# Driver.net
KiCad netlist of a schematic drawn in EAGLE
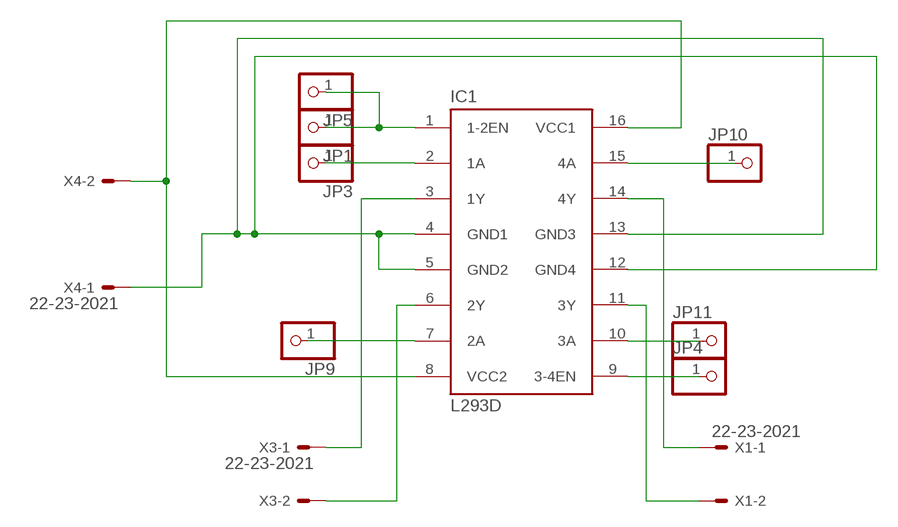
[diagram p0: schematic, sheet 1]

(export (version "E")
  (design (tool "Eeschema 10.0.6"))
  (components
    (comp (ref "IC1")
      (value "L293D")
      (footprint "eagle-import:DIL16")
      (libsource (lib "eagle-import") (part "L293D"))
    )
    (comp (ref "JP1")
      (value "PINHD-1X1")
      (footprint "eagle-import:1X01")
      (libsource (lib "eagle-import") (part "PINHD-1X1"))
    )
    (comp (ref "JP3")
      (value "PINHD-1X1")
      (footprint "eagle-import:1X01")
      (libsource (lib "eagle-import") (part "PINHD-1X1"))
    )
    (comp (ref "JP4")
      (value "PINHD-1X1")
      (footprint "eagle-import:1X01")
      (libsource (lib "eagle-import") (part "PINHD-1X1"))
    )
    (comp (ref "JP5")
      (value "PINHD-1X1")
      (footprint "eagle-import:1X01")
      (libsource (lib "eagle-import") (part "PINHD-1X1"))
    )
    (comp (ref "JP9")
      (value "PINHD-1X1")
      (footprint "eagle-import:1X01")
      (libsource (lib "eagle-import") (part "PINHD-1X1"))
    )
    (comp (ref "JP10")
      (value "PINHD-1X1")
      (footprint "eagle-import:1X01")
      (libsource (lib "eagle-import") (part "PINHD-1X1"))
    )
    (comp (ref "JP11")
      (value "PINHD-1X1")
      (footprint "eagle-import:1X01")
      (libsource (lib "eagle-import") (part "PINHD-1X1"))
    )
    (comp (ref "X1")
      (value "22-23-2021")
      (footprint "eagle-import:22-23-2021")
      (fields (field (name "MF") "MOLEX"))
      (libsource (lib "eagle-import") (part "22-23-2021"))
    )
    (comp (ref "X3")
      (value "22-23-2021")
      (footprint "eagle-import:22-23-2021")
      (fields (field (name "MF") "MOLEX"))
      (libsource (lib "eagle-import") (part "22-23-2021"))
    )
    (comp (ref "X4")
      (value "22-23-2021")
      (footprint "eagle-import:22-23-2021")
      (fields (field (name "MF") "MOLEX"))
      (libsource (lib "eagle-import") (part "22-23-2021"))
    )
  )
  (nets
    (net (code "1") (name "Net-(IC1-1-2EN)") (class "Default")
      (node (ref "IC1") (pin "1") (pinfunction "1-2EN_1") (pintype "input"))
      (node (ref "JP1") (pin "1") (pinfunction "1_1") (pintype "passive"))
      (node (ref "JP5") (pin "1") (pinfunction "1_1") (pintype "passive"))
    )
    (net (code "2") (name "Net-(IC1-1A)") (class "Default")
      (node (ref "IC1") (pin "2") (pinfunction "1A_2") (pintype "input"))
      (node (ref "JP3") (pin "1") (pinfunction "1_1") (pintype "passive"))
    )
    (net (code "3") (name "Net-(IC1-1Y)") (class "Default")
      (node (ref "IC1") (pin "3") (pinfunction "1Y_3") (pintype "output"))
      (node (ref "X3") (pin "1") (pinfunction "S_1") (pintype "passive"))
    )
    (net (code "4") (name "Net-(IC1-2A)") (class "Default")
      (node (ref "IC1") (pin "7") (pinfunction "2A_7") (pintype "input"))
      (node (ref "JP9") (pin "1") (pinfunction "1_1") (pintype "passive"))
    )
    (net (code "5") (name "Net-(IC1-2Y)") (class "Default")
      (node (ref "IC1") (pin "6") (pinfunction "2Y_6") (pintype "output"))
      (node (ref "X3") (pin "2") (pinfunction "S_2") (pintype "passive"))
    )
    (net (code "6") (name "Net-(IC1-3-4EN)") (class "Default")
      (node (ref "IC1") (pin "9") (pinfunction "3-4EN_9") (pintype "input"))
      (node (ref "JP4") (pin "1") (pinfunction "1_1") (pintype "passive"))
    )
    (net (code "7") (name "Net-(IC1-3A)") (class "Default")
      (node (ref "IC1") (pin "10") (pinfunction "3A_10") (pintype "input"))
      (node (ref "JP11") (pin "1") (pinfunction "1_1") (pintype "passive"))
    )
    (net (code "8") (name "Net-(IC1-3Y)") (class "Default")
      (node (ref "IC1") (pin "11") (pinfunction "3Y_11") (pintype "output"))
      (node (ref "X1") (pin "2") (pinfunction "S_2") (pintype "passive"))
    )
    (net (code "9") (name "Net-(IC1-4A)") (class "Default")
      (node (ref "IC1") (pin "15") (pinfunction "4A_15") (pintype "input"))
      (node (ref "JP10") (pin "1") (pinfunction "1_1") (pintype "passive"))
    )
    (net (code "10") (name "Net-(IC1-4Y)") (class "Default")
      (node (ref "IC1") (pin "14") (pinfunction "4Y_14") (pintype "output"))
      (node (ref "X1") (pin "1") (pinfunction "S_1") (pintype "passive"))
    )
    (net (code "11") (name "Net-(IC1-GND1)") (class "Default")
      (node (ref "IC1") (pin "12") (pinfunction "GND4_12") (pintype "power_in"))
      (node (ref "IC1") (pin "13") (pinfunction "GND3_13") (pintype "power_in"))
      (node (ref "IC1") (pin "4") (pinfunction "GND1_4") (pintype "power_in"))
      (node (ref "IC1") (pin "5") (pinfunction "GND2_5") (pintype "power_in"))
      (node (ref "X4") (pin "1") (pinfunction "S_1") (pintype "passive"))
    )
    (net (code "12") (name "Net-(IC1-VCC1)") (class "Default")
      (node (ref "IC1") (pin "16") (pinfunction "VCC1_16") (pintype "power_in"))
      (node (ref "IC1") (pin "8") (pinfunction "VCC2_8") (pintype "power_in"))
      (node (ref "X4") (pin "2") (pinfunction "S_2") (pintype "passive"))
    )
  )
)
